# DAC.net
KiCad netlist of a schematic drawn in Altium Designer
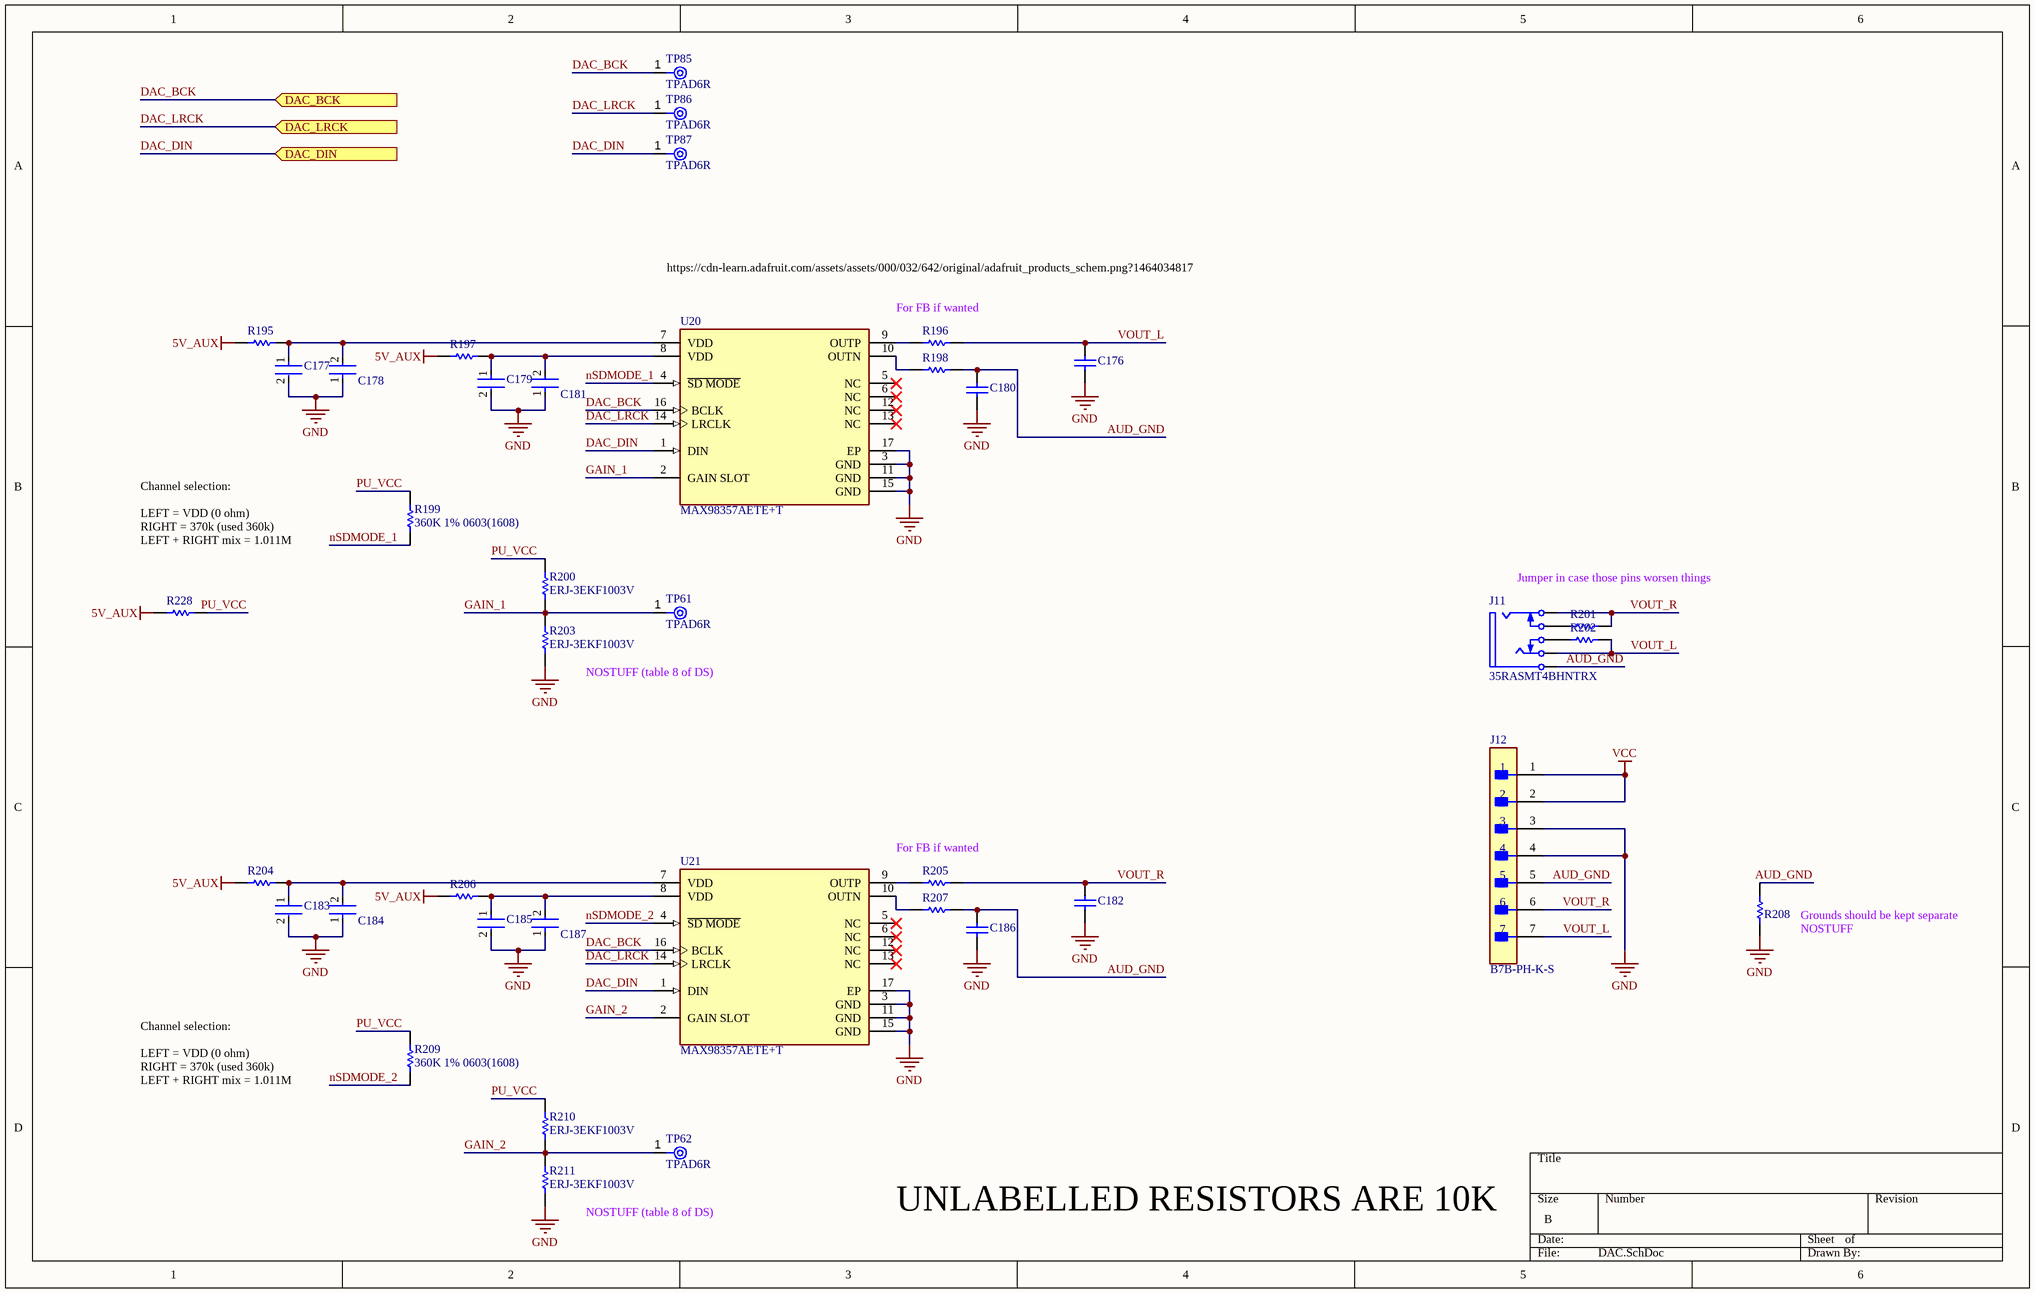
[diagram p0: DAC.SchDoc]

(export (version "E")
  (design (tool "Eeschema 10.0.6"))
  (components
    (comp (ref "C176")
      (value "C0805C221K5RACTU")
      (footprint "CAPC2013X88X50ML20T25")
      (fields (field (name "MANUFACTURER") "Kemet"))
      (libsource (lib "Altium Content Vault") (part "CAP"))
    )
    (comp (ref "C177")
      (value "CL05A106MP5NUNC")
      (footprint "FP-CL05A106MP5NUNC-MFG")
      (description "CAP CER 10UF 10V X5R 0402")
      (fields
        (field (name "OCTOPART") "https://octopart.com/cl05a106mp5nunc-samsung-22457395")
        (field (name "TOLERANCE") "20%")
      )
      (libsource (lib "Altium Content Vault") (part "b4654b650e69147ec39a6b967a45e02"))
    )
    (comp (ref "C178")
      (value "C1005X7R1H104K050BB")
      (footprint "FP-C1005-050-0_05-IPC_C")
      (description "Multilayer Ceramic Capacitors 100nF ±10% 50V X7R SMD 0402")
      (fields (field (name "VOLTAGE") "50V") (field (name "TOLERANCE") "10%"))
      (libsource (lib "Altium Content Vault") (part "b4654b650e69147ec39a6b967a45e02"))
    )
    (comp (ref "C179")
      (value "CL05A106MP5NUNC")
      (footprint "FP-CL05A106MP5NUNC-MFG")
      (description "CAP CER 10UF 10V X5R 0402")
      (fields
        (field (name "OCTOPART") "https://octopart.com/cl05a106mp5nunc-samsung-22457395")
        (field (name "TOLERANCE") "20%")
      )
      (libsource (lib "Altium Content Vault") (part "b4654b650e69147ec39a6b967a45e02"))
    )
    (comp (ref "C180")
      (value "C0805C221K5RACTU")
      (footprint "CAPC2013X88X50ML20T25")
      (fields (field (name "MANUFACTURER") "Kemet"))
      (libsource (lib "Altium Content Vault") (part "CAP"))
    )
    (comp (ref "C181")
      (value "C1005X7R1H104K050BB")
      (footprint "FP-C1005-050-0_05-IPC_C")
      (description "Multilayer Ceramic Capacitors 100nF ±10% 50V X7R SMD 0402")
      (fields (field (name "VOLTAGE") "50V") (field (name "TOLERANCE") "10%"))
      (libsource (lib "Altium Content Vault") (part "b4654b650e69147ec39a6b967a45e02"))
    )
    (comp (ref "C182")
      (value "C0805C221K5RACTU")
      (footprint "CAPC2013X88X50ML20T25")
      (fields (field (name "MANUFACTURER") "Kemet"))
      (libsource (lib "Altium Content Vault") (part "CAP"))
    )
    (comp (ref "C183")
      (value "CL05A106MP5NUNC")
      (footprint "FP-CL05A106MP5NUNC-MFG")
      (description "CAP CER 10UF 10V X5R 0402")
      (fields
        (field (name "OCTOPART") "https://octopart.com/cl05a106mp5nunc-samsung-22457395")
        (field (name "TOLERANCE") "20%")
      )
      (libsource (lib "Altium Content Vault") (part "b4654b650e69147ec39a6b967a45e02"))
    )
    (comp (ref "C184")
      (value "C1005X7R1H104K050BB")
      (footprint "FP-C1005-050-0_05-IPC_C")
      (description "Multilayer Ceramic Capacitors 100nF ±10% 50V X7R SMD 0402")
      (fields (field (name "VOLTAGE") "50V") (field (name "TOLERANCE") "10%"))
      (libsource (lib "Altium Content Vault") (part "b4654b650e69147ec39a6b967a45e02"))
    )
    (comp (ref "C185")
      (value "CL05A106MP5NUNC")
      (footprint "FP-CL05A106MP5NUNC-MFG")
      (description "CAP CER 10UF 10V X5R 0402")
      (fields
        (field (name "OCTOPART") "https://octopart.com/cl05a106mp5nunc-samsung-22457395")
        (field (name "TOLERANCE") "20%")
      )
      (libsource (lib "Altium Content Vault") (part "b4654b650e69147ec39a6b967a45e02"))
    )
    (comp (ref "C186")
      (value "C0805C221K5RACTU")
      (footprint "CAPC2013X88X50ML20T25")
      (fields (field (name "MANUFACTURER") "Kemet"))
      (libsource (lib "Altium Content Vault") (part "CAP"))
    )
    (comp (ref "C187")
      (value "C1005X7R1H104K050BB")
      (footprint "FP-C1005-050-0_05-IPC_C")
      (description "Multilayer Ceramic Capacitors 100nF ±10% 50V X7R SMD 0402")
      (fields (field (name "VOLTAGE") "50V") (field (name "TOLERANCE") "10%"))
      (libsource (lib "Altium Content Vault") (part "b4654b650e69147ec39a6b967a45e02"))
    )
    (comp (ref "J11")
      (value "35RASMT4BHNTRX")
      (footprint "SWIT-35RASMT4BHNTRX_V")
      (description "Female 3.5 mm Phone Jack, 5 Position, Height 5 mm, RoHS, Tape and Reel")
      (libsource (lib "Altium Content Vault") (part "JACK-3CD5-RN"))
    )
    (comp (ref "J12")
      (value "B7B-PH-K-S")
      (footprint "FP-B7B-PH-K-S-MFG")
      (description "CONN HEADER VERT 7POS 2MM")
      (libsource (lib "Altium Content Vault") (part "5bcee6b94e1fee4be3f4cc3a650a442"))
    )
    (comp (ref "R195")
      (value "RC0402JR-070RL")
      (footprint "RESC1005X40X25NL05T10")
      (fields (field (name "MANUFACTURER") "Yageo / Phycomp"))
      (libsource (lib "Altium Content Vault") (part "RES"))
    )
    (comp (ref "R196")
      (value "RC0603JR-070RL")
      (footprint "RESC1608X55X25ML10T15")
      (description "Chip Resistor, 0 Ohm, +/- 5%, 0.1 W, -55 to 155 degC, 0603 (1608 Metric), RoHS, Tape and Reel")
      (fields (field (name "TOLERANCE") "5%") (field (name "MANUFACTURER") "Yageo"))
      (libsource (lib "Altium Content Vault") (part "RES-2"))
    )
    (comp (ref "R197")
      (value "RC0402JR-070RL")
      (footprint "RESC1005X40X25NL05T10")
      (fields (field (name "MANUFACTURER") "Yageo / Phycomp"))
      (libsource (lib "Altium Content Vault") (part "RES"))
    )
    (comp (ref "R198")
      (value "RC0603JR-070RL")
      (footprint "RESC1608X55X25ML10T15")
      (description "Chip Resistor, 0 Ohm, +/- 5%, 0.1 W, -55 to 155 degC, 0603 (1608 Metric), RoHS, Tape and Reel")
      (fields (field (name "TOLERANCE") "5%") (field (name "MANUFACTURER") "Yageo"))
      (libsource (lib "Altium Content Vault") (part "RES-2"))
    )
    (comp (ref "R199")
      (value "360K 1% 0603(1608)")
      (footprint "RESC0603(1608)_M")
      (description "360K 0.1W 1% 0603 (1608 Metric)  SMD")
      (fields (field (name "POWER") "0.1 W") (field (name "TOLERANCE") "1 %"))
      (libsource (lib "Altium Content Vault") (part "RES"))
    )
    (comp (ref "R200")
      (value "ERJ-3EKF1003V")
      (footprint "RESC1608X55X30ML15T15")
      (fields (field (name "MANUFACTURER") "Panasonic"))
      (libsource (lib "Altium Content Vault") (part "RES"))
    )
    (comp (ref "R201")
      (value "RC0402JR-070RL")
      (footprint "RESC1005X40X25NL05T10")
      (fields (field (name "MANUFACTURER") "Yageo / Phycomp"))
      (libsource (lib "Altium Content Vault") (part "RES"))
    )
    (comp (ref "R202")
      (value "RC0402JR-070RL")
      (footprint "RESC1005X40X25NL05T10")
      (fields (field (name "MANUFACTURER") "Yageo / Phycomp"))
      (libsource (lib "Altium Content Vault") (part "RES"))
    )
    (comp (ref "R203")
      (value "ERJ-3EKF1003V")
      (footprint "RESC1608X55X30ML15T15")
      (fields (field (name "MANUFACTURER") "Panasonic"))
      (libsource (lib "Altium Content Vault") (part "RES"))
    )
    (comp (ref "R204")
      (value "RC0402JR-070RL")
      (footprint "RESC1005X40X25NL05T10")
      (fields (field (name "MANUFACTURER") "Yageo / Phycomp"))
      (libsource (lib "Altium Content Vault") (part "RES"))
    )
    (comp (ref "R205")
      (value "RC0603JR-070RL")
      (footprint "RESC1608X55X25ML10T15")
      (description "Chip Resistor, 0 Ohm, +/- 5%, 0.1 W, -55 to 155 degC, 0603 (1608 Metric), RoHS, Tape and Reel")
      (fields (field (name "TOLERANCE") "5%") (field (name "MANUFACTURER") "Yageo"))
      (libsource (lib "Altium Content Vault") (part "RES-2"))
    )
    (comp (ref "R206")
      (value "RC0402JR-070RL")
      (footprint "RESC1005X40X25NL05T10")
      (fields (field (name "MANUFACTURER") "Yageo / Phycomp"))
      (libsource (lib "Altium Content Vault") (part "RES"))
    )
    (comp (ref "R207")
      (value "RC0603JR-070RL")
      (footprint "RESC1608X55X25ML10T15")
      (description "Chip Resistor, 0 Ohm, +/- 5%, 0.1 W, -55 to 155 degC, 0603 (1608 Metric), RoHS, Tape and Reel")
      (fields (field (name "TOLERANCE") "5%") (field (name "MANUFACTURER") "Yageo"))
      (libsource (lib "Altium Content Vault") (part "RES-2"))
    )
    (comp (ref "R208")
      (value "RC0603JR-070RL")
      (footprint "RESC1608X55X25ML10T15")
      (description "Chip Resistor, 0 Ohm, +/- 5%, 0.1 W, -55 to 155 degC, 0603 (1608 Metric), RoHS, Tape and Reel")
      (fields (field (name "TOLERANCE") "5%") (field (name "MANUFACTURER") "Yageo"))
      (libsource (lib "Altium Content Vault") (part "RES-2"))
    )
    (comp (ref "R209")
      (value "360K 1% 0603(1608)")
      (footprint "RESC0603(1608)_M")
      (description "360K 0.1W 1% 0603 (1608 Metric)  SMD")
      (fields (field (name "POWER") "0.1 W") (field (name "TOLERANCE") "1 %"))
      (libsource (lib "Altium Content Vault") (part "RES"))
    )
    (comp (ref "R210")
      (value "ERJ-3EKF1003V")
      (footprint "RESC1608X55X30ML15T15")
      (fields (field (name "MANUFACTURER") "Panasonic"))
      (libsource (lib "Altium Content Vault") (part "RES"))
    )
    (comp (ref "R211")
      (value "ERJ-3EKF1003V")
      (footprint "RESC1608X55X30ML15T15")
      (fields (field (name "MANUFACTURER") "Panasonic"))
      (libsource (lib "Altium Content Vault") (part "RES"))
    )
    (comp (ref "R228")
      (value "RC0402JR-070RL")
      (footprint "RESC1005X40X25NL05T10")
      (fields (field (name "MANUFACTURER") "Yageo / Phycomp"))
      (libsource (lib "Altium Content Vault") (part "RES"))
    )
    (comp (ref "TP61")
      (value "TPAD6R")
      (footprint "New footprint 1")
      (description "Test Point .6mm")
      (libsource (lib "Space Concordia") (part "TP"))
    )
    (comp (ref "TP62")
      (value "TPAD6R")
      (footprint "New footprint 1")
      (description "Test Point .6mm")
      (libsource (lib "Space Concordia") (part "TP"))
    )
    (comp (ref "TP85")
      (value "TPAD6R")
      (footprint "New footprint 1")
      (description "Test Point .6mm")
      (libsource (lib "Space Concordia") (part "TP"))
    )
    (comp (ref "TP86")
      (value "TPAD6R")
      (footprint "New footprint 1")
      (description "Test Point .6mm")
      (libsource (lib "Space Concordia") (part "TP"))
    )
    (comp (ref "TP87")
      (value "TPAD6R")
      (footprint "New footprint 1")
      (description "Test Point .6mm")
      (libsource (lib "Space Concordia") (part "TP"))
    )
    (comp (ref "U20")
      (value "MAX98357AETE+T")
      (footprint "FP-T1633-4-MFG")
      (description "IC AMP CLASS D MONO 3.2W 16TQFN")
      (libsource (lib "Altium Content Vault") (part "902df0143a84dfa2dd990dcc5368a09"))
    )
    (comp (ref "U21")
      (value "MAX98357AETE+T")
      (footprint "FP-T1633-4-MFG")
      (description "IC AMP CLASS D MONO 3.2W 16TQFN")
      (libsource (lib "Altium Content Vault") (part "902df0143a84dfa2dd990dcc5368a09"))
    )
  )
  (nets
    (net (code "1") (name "/AUD_GND") (class "Default")
      (node (ref "C180") (pin "2") (pinfunction "2_2") (pintype "passive"))
      (node (ref "C186") (pin "2") (pinfunction "2_2") (pintype "passive"))
      (node (ref "J11") (pin "1") (pinfunction "1_1") (pintype "passive"))
      (node (ref "J12") (pin "5") (pinfunction "5_5") (pintype "passive"))
      (node (ref "R198") (pin "2") (pinfunction "2_2") (pintype "passive"))
      (node (ref "R207") (pin "2") (pinfunction "2_2") (pintype "passive"))
      (node (ref "R208") (pin "1") (pinfunction "1_1") (pintype "passive"))
    )
    (net (code "2") (name "/DAC_BCK") (class "Default")
      (node (ref "TP85") (pin "1") (pinfunction "TP_1") (pintype "passive"))
      (node (ref "U20") (pin "16") (pinfunction "BCLK_16") (pintype "input"))
      (node (ref "U21") (pin "16") (pinfunction "BCLK_16") (pintype "input"))
    )
    (net (code "3") (name "/DAC_DIN") (class "Default")
      (node (ref "TP87") (pin "1") (pinfunction "TP_1") (pintype "passive"))
      (node (ref "U20") (pin "1") (pinfunction "DIN_1") (pintype "input"))
      (node (ref "U21") (pin "1") (pinfunction "DIN_1") (pintype "input"))
    )
    (net (code "4") (name "/DAC_LRCK") (class "Default")
      (node (ref "TP86") (pin "1") (pinfunction "TP_1") (pintype "passive"))
      (node (ref "U20") (pin "14") (pinfunction "LRCLK_14") (pintype "input"))
      (node (ref "U21") (pin "14") (pinfunction "LRCLK_14") (pintype "input"))
    )
    (net (code "5") (name "/GAIN_1") (class "Default")
      (node (ref "R200") (pin "1") (pinfunction "1_1") (pintype "passive"))
      (node (ref "R203") (pin "2") (pinfunction "2_2") (pintype "passive"))
      (node (ref "TP61") (pin "1") (pinfunction "TP_1") (pintype "passive"))
      (node (ref "U20") (pin "2") (pinfunction "GAIN_SLOT_2") (pintype "passive"))
    )
    (net (code "6") (name "/GAIN_2") (class "Default")
      (node (ref "R210") (pin "1") (pinfunction "1_1") (pintype "passive"))
      (node (ref "R211") (pin "2") (pinfunction "2_2") (pintype "passive"))
      (node (ref "TP62") (pin "1") (pinfunction "TP_1") (pintype "passive"))
      (node (ref "U21") (pin "2") (pinfunction "GAIN_SLOT_2") (pintype "passive"))
    )
    (net (code "7") (name "/PU_VCC") (class "Default")
      (node (ref "R199") (pin "2") (pinfunction "2_2") (pintype "passive"))
      (node (ref "R200") (pin "2") (pinfunction "2_2") (pintype "passive"))
      (node (ref "R209") (pin "2") (pinfunction "2_2") (pintype "passive"))
      (node (ref "R210") (pin "2") (pinfunction "2_2") (pintype "passive"))
      (node (ref "R228") (pin "2") (pinfunction "2_2") (pintype "passive"))
    )
    (net (code "8") (name "/VOUT_L") (class "Default")
      (node (ref "C176") (pin "2") (pinfunction "2_2") (pintype "passive"))
      (node (ref "J11") (pin "3") (pinfunction "3_3") (pintype "passive"))
      (node (ref "J12") (pin "7") (pinfunction "7_7") (pintype "passive"))
      (node (ref "R196") (pin "2") (pinfunction "2_2") (pintype "passive"))
      (node (ref "R202") (pin "2") (pinfunction "2_2") (pintype "passive"))
    )
    (net (code "9") (name "/VOUT_R") (class "Default")
      (node (ref "C182") (pin "2") (pinfunction "2_2") (pintype "passive"))
      (node (ref "J11") (pin "2") (pinfunction "2_2") (pintype "passive"))
      (node (ref "J12") (pin "6") (pinfunction "6_6") (pintype "passive"))
      (node (ref "R201") (pin "2") (pinfunction "2_2") (pintype "passive"))
      (node (ref "R205") (pin "2") (pinfunction "2_2") (pintype "passive"))
    )
    (net (code "10") (name "/nSDMODE_1") (class "Default")
      (node (ref "R199") (pin "1") (pinfunction "1_1") (pintype "passive"))
      (node (ref "U20") (pin "4") (pinfunction "~{SD_MODE}_4") (pintype "input"))
    )
    (net (code "11") (name "/nSDMODE_2") (class "Default")
      (node (ref "R209") (pin "1") (pinfunction "1_1") (pintype "passive"))
      (node (ref "U21") (pin "4") (pinfunction "~{SD_MODE}_4") (pintype "input"))
    )
    (net (code "12") (name "5V_AUX") (class "Default")
      (node (ref "R195") (pin "1") (pinfunction "1_1") (pintype "passive"))
      (node (ref "R197") (pin "1") (pinfunction "1_1") (pintype "passive"))
      (node (ref "R204") (pin "1") (pinfunction "1_1") (pintype "passive"))
      (node (ref "R206") (pin "1") (pinfunction "1_1") (pintype "passive"))
      (node (ref "R228") (pin "1") (pinfunction "1_1") (pintype "passive"))
    )
    (net (code "13") (name "GND") (class "Default")
      (node (ref "C176") (pin "1") (pinfunction "1_1") (pintype "passive"))
      (node (ref "C177") (pin "2") (pinfunction "2_2") (pintype "passive"))
      (node (ref "C178") (pin "1") (pinfunction "1_1") (pintype "passive"))
      (node (ref "C179") (pin "2") (pinfunction "2_2") (pintype "passive"))
      (node (ref "C180") (pin "1") (pinfunction "1_1") (pintype "passive"))
      (node (ref "C181") (pin "1") (pinfunction "1_1") (pintype "passive"))
      (node (ref "C182") (pin "1") (pinfunction "1_1") (pintype "passive"))
      (node (ref "C183") (pin "2") (pinfunction "2_2") (pintype "passive"))
      (node (ref "C184") (pin "1") (pinfunction "1_1") (pintype "passive"))
      (node (ref "C185") (pin "2") (pinfunction "2_2") (pintype "passive"))
      (node (ref "C186") (pin "1") (pinfunction "1_1") (pintype "passive"))
      (node (ref "C187") (pin "1") (pinfunction "1_1") (pintype "passive"))
      (node (ref "J12") (pin "3") (pinfunction "3_3") (pintype "passive"))
      (node (ref "J12") (pin "4") (pinfunction "4_4") (pintype "passive"))
      (node (ref "R203") (pin "1") (pinfunction "1_1") (pintype "passive"))
      (node (ref "R208") (pin "2") (pinfunction "2_2") (pintype "passive"))
      (node (ref "R211") (pin "1") (pinfunction "1_1") (pintype "passive"))
      (node (ref "U20") (pin "11") (pinfunction "GND_11") (pintype "power_in"))
      (node (ref "U20") (pin "15") (pinfunction "GND_15") (pintype "power_in"))
      (node (ref "U20") (pin "17") (pinfunction "EP_17") (pintype "passive"))
      (node (ref "U20") (pin "3") (pinfunction "GND_3") (pintype "power_in"))
      (node (ref "U21") (pin "11") (pinfunction "GND_11") (pintype "power_in"))
      (node (ref "U21") (pin "15") (pinfunction "GND_15") (pintype "power_in"))
      (node (ref "U21") (pin "17") (pinfunction "EP_17") (pintype "passive"))
      (node (ref "U21") (pin "3") (pinfunction "GND_3") (pintype "power_in"))
    )
    (net (code "14") (name "Net-(C177-Pad1)") (class "Default")
      (node (ref "C177") (pin "1") (pinfunction "1_1") (pintype "passive"))
      (node (ref "C178") (pin "2") (pinfunction "2_2") (pintype "passive"))
      (node (ref "R195") (pin "2") (pinfunction "2_2") (pintype "passive"))
      (node (ref "U20") (pin "7") (pinfunction "VDD_7") (pintype "power_in"))
    )
    (net (code "15") (name "Net-(C179-Pad1)") (class "Default")
      (node (ref "C179") (pin "1") (pinfunction "1_1") (pintype "passive"))
      (node (ref "C181") (pin "2") (pinfunction "2_2") (pintype "passive"))
      (node (ref "R197") (pin "2") (pinfunction "2_2") (pintype "passive"))
      (node (ref "U20") (pin "8") (pinfunction "VDD_8") (pintype "power_in"))
    )
    (net (code "16") (name "Net-(C183-Pad1)") (class "Default")
      (node (ref "C183") (pin "1") (pinfunction "1_1") (pintype "passive"))
      (node (ref "C184") (pin "2") (pinfunction "2_2") (pintype "passive"))
      (node (ref "R204") (pin "2") (pinfunction "2_2") (pintype "passive"))
      (node (ref "U21") (pin "7") (pinfunction "VDD_7") (pintype "power_in"))
    )
    (net (code "17") (name "Net-(C185-Pad1)") (class "Default")
      (node (ref "C185") (pin "1") (pinfunction "1_1") (pintype "passive"))
      (node (ref "C187") (pin "2") (pinfunction "2_2") (pintype "passive"))
      (node (ref "R206") (pin "2") (pinfunction "2_2") (pintype "passive"))
      (node (ref "U21") (pin "8") (pinfunction "VDD_8") (pintype "power_in"))
    )
    (net (code "18") (name "Net-(J11-Pad4)") (class "Default")
      (node (ref "J11") (pin "4") (pinfunction "4_4") (pintype "passive"))
      (node (ref "R201") (pin "1") (pinfunction "1_1") (pintype "passive"))
    )
    (net (code "19") (name "Net-(J11-Pad5)") (class "Default")
      (node (ref "J11") (pin "5") (pinfunction "5_5") (pintype "passive"))
      (node (ref "R202") (pin "1") (pinfunction "1_1") (pintype "passive"))
    )
    (net (code "20") (name "Net-(U20-OUTN)") (class "Default")
      (node (ref "R198") (pin "1") (pinfunction "1_1") (pintype "passive"))
      (node (ref "U20") (pin "10") (pinfunction "OUTN_10") (pintype "passive"))
    )
    (net (code "21") (name "Net-(U20-OUTP)") (class "Default")
      (node (ref "R196") (pin "1") (pinfunction "1_1") (pintype "passive"))
      (node (ref "U20") (pin "9") (pinfunction "OUTP_9") (pintype "passive"))
    )
    (net (code "22") (name "Net-(U21-OUTN)") (class "Default")
      (node (ref "R207") (pin "1") (pinfunction "1_1") (pintype "passive"))
      (node (ref "U21") (pin "10") (pinfunction "OUTN_10") (pintype "passive"))
    )
    (net (code "23") (name "Net-(U21-OUTP)") (class "Default")
      (node (ref "R205") (pin "1") (pinfunction "1_1") (pintype "passive"))
      (node (ref "U21") (pin "9") (pinfunction "OUTP_9") (pintype "passive"))
    )
    (net (code "24") (name "VCC") (class "Default")
      (node (ref "J12") (pin "1") (pinfunction "1_1") (pintype "passive"))
      (node (ref "J12") (pin "2") (pinfunction "2_2") (pintype "passive"))
    )
    (net (code "25") (name "unconnected-(U20-NC-Pad5)") (class "Default")
      (node (ref "U20") (pin "5") (pinfunction "NC_5") (pintype "passive+no_connect"))
    )
    (net (code "26") (name "unconnected-(U20-NC-Pad6)") (class "Default")
      (node (ref "U20") (pin "6") (pinfunction "NC_6") (pintype "passive+no_connect"))
    )
    (net (code "27") (name "unconnected-(U20-NC-Pad12)") (class "Default")
      (node (ref "U20") (pin "12") (pinfunction "NC_12") (pintype "passive+no_connect"))
    )
    (net (code "28") (name "unconnected-(U20-NC-Pad13)") (class "Default")
      (node (ref "U20") (pin "13") (pinfunction "NC_13") (pintype "passive+no_connect"))
    )
    (net (code "29") (name "unconnected-(U21-NC-Pad5)") (class "Default")
      (node (ref "U21") (pin "5") (pinfunction "NC_5") (pintype "passive+no_connect"))
    )
    (net (code "30") (name "unconnected-(U21-NC-Pad6)") (class "Default")
      (node (ref "U21") (pin "6") (pinfunction "NC_6") (pintype "passive+no_connect"))
    )
    (net (code "31") (name "unconnected-(U21-NC-Pad12)") (class "Default")
      (node (ref "U21") (pin "12") (pinfunction "NC_12") (pintype "passive+no_connect"))
    )
    (net (code "32") (name "unconnected-(U21-NC-Pad13)") (class "Default")
      (node (ref "U21") (pin "13") (pinfunction "NC_13") (pintype "passive+no_connect"))
    )
  )
)
